# P11_Exp_Conn_uSD_and.net
KiCad netlist of a schematic drawn in Altium Designer
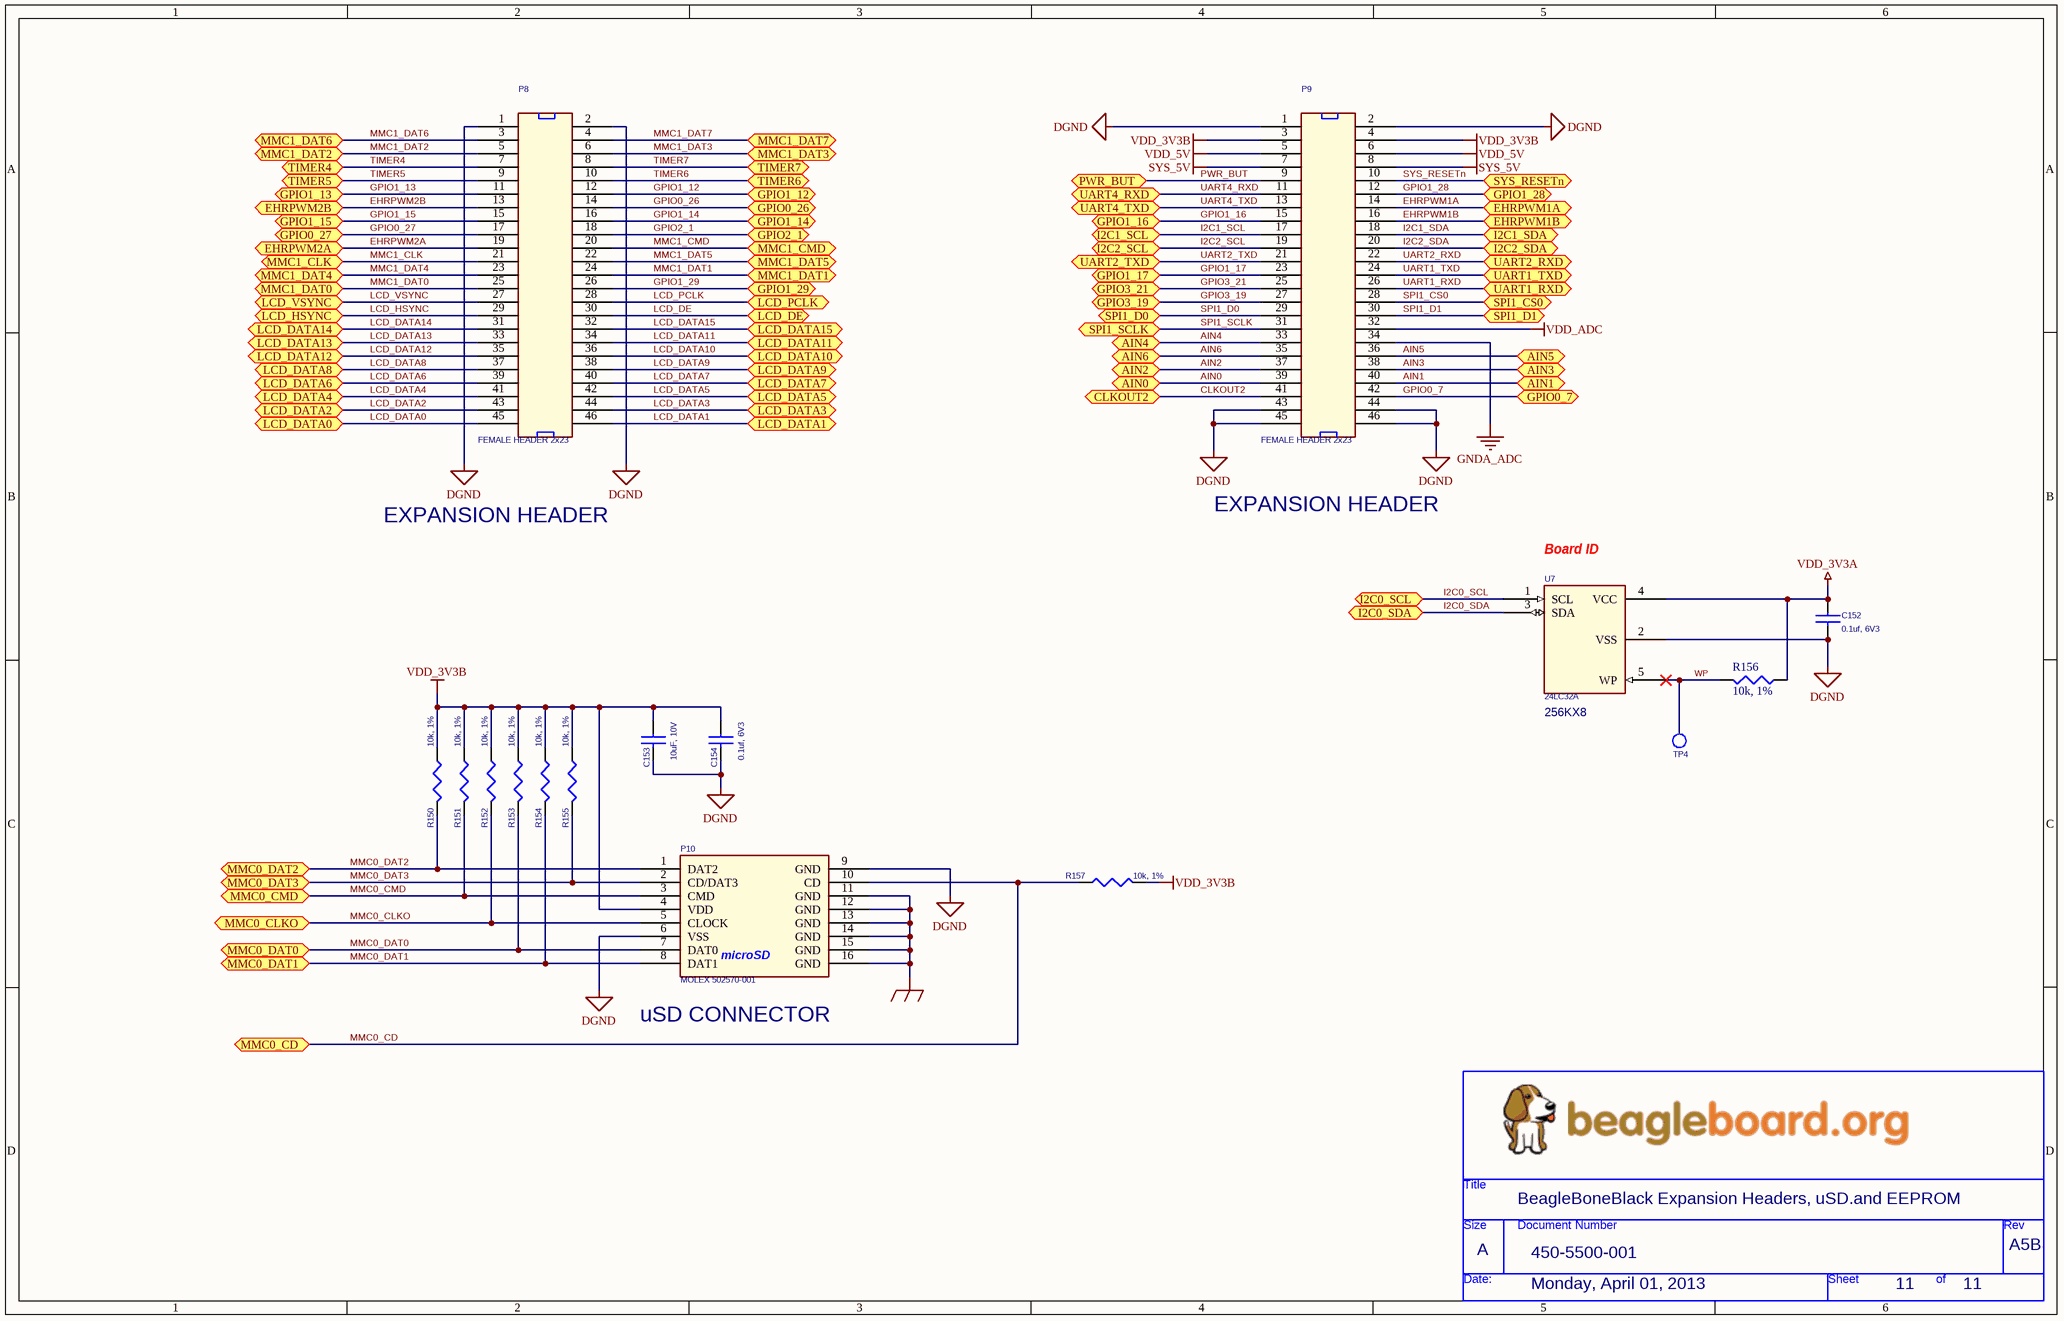
[diagram p0: P11_Exp Conn, uSD, and .SchDoc]

(export (version "E")
  (design (tool "Eeschema 10.0.6"))
  (components
    (comp (ref "C152")
      (value "0.1uf, 6V3")
      (footprint "402")
      (description "CAP CER 0.1UF 6.3V 10% X5R 0402")
      (fields
        (field (name "MANUFACTURER") "TDK Corporation")
        (field (name "MANUFACTURER PART NUMBER") "C1005X5R0J104K050BA")
      )
      (libsource (lib "BEAGLEBONEBLACK_REV A5B") (part "CAP_0.1uF_X7R_16V_10% 0402"))
    )
    (comp (ref "C153")
      (value "10uF, 10V")
      (description "CAP CER 10UF 10V Y5V 0805")
      (fields
        (field (name "MANUFACTURER") "TDK Corporation")
        (field (name "MANUFACTURER PART NUMBER") "C2012Y5V1A106Z")
      )
      (libsource (lib "BEAGLEBONEBLACK_REV A5B") (part "CAP_10uF_Y5V_10V_10%_0805"))
    )
    (comp (ref "C154")
      (value "0.1uf, 6V3")
      (footprint "402")
      (description "CAP CER 0.1UF 6.3V 10% X5R 0402")
      (fields
        (field (name "MANUFACTURER") "TDK Corporation")
        (field (name "MANUFACTURER PART NUMBER") "C1005X5R0J104K050BA")
      )
      (libsource (lib "BEAGLEBONEBLACK_REV A5B") (part "CAP_0.1uF_X7R_16V_10% 0402"))
    )
    (comp (ref "P8")
      (value "FEMALE HEADER 2x23")
      (description "CONN HEADER FMAL 46PS.1\" DL GOLD")
      (fields
        (field (name "MANUFACTURER") "Sullins Connector Solutions")
        (field (name "MANUFACTURER PART NUMBER") "PPPC232LFBN-RC")
      )
      (libsource (lib "BEAGLEBONEBLACK_REV A5B") (part "HDR_46_F_2_0.1_0.1"))
    )
    (comp (ref "P9")
      (value "FEMALE HEADER 2x23")
      (description "CONN HEADER FMAL 46PS.1\" DL GOLD")
      (fields
        (field (name "MANUFACTURER") "Sullins Connector Solutions")
        (field (name "MANUFACTURER PART NUMBER") "PPPC232LFBN-RC")
      )
      (libsource (lib "BEAGLEBONEBLACK_REV A5B") (part "HDR_46_F_2_0.1_0.1"))
    )
    (comp (ref "P10")
      (value "MOLEX 502570-001")
      (footprint "SD-MICRO-SCHA5B0300")
      (description "CONN MICRO SD R/A PUSH-PUSH SMD")
      (fields
        (field (name "MANUFACTURER") "Molex Inc")
        (field (name "MANUFACTURER PART NUMBER") "5025700893")
      )
      (libsource (lib "BEAGLEBONEBLACK_REV A5B") (part "microSD_CONN_2"))
    )
    (comp (ref "R150")
      (value "10k, 1%")
      (footprint "402")
      (description "RES 10K OHM 1/16W 5% 0402 SMD")
      (fields
        (field (name "MANUFACTURER") "Rohm Semiconductor")
        (field (name "MANUFACTURER PART NUMBER") "MCR01MZPJ103")
      )
      (libsource (lib "BEAGLEBONEBLACK_REV A5B") (part "RES_10K_1/16W_1%_0402"))
    )
    (comp (ref "R151")
      (value "10k, 1%")
      (footprint "402")
      (description "RES 10K OHM 1/16W 5% 0402 SMD")
      (fields
        (field (name "MANUFACTURER") "Rohm Semiconductor")
        (field (name "MANUFACTURER PART NUMBER") "MCR01MZPJ103")
      )
      (libsource (lib "BEAGLEBONEBLACK_REV A5B") (part "RES_10K_1/16W_1%_0402"))
    )
    (comp (ref "R152")
      (value "10k, 1%")
      (footprint "402")
      (description "RES 10K OHM 1/16W 5% 0402 SMD")
      (fields
        (field (name "MANUFACTURER") "Rohm Semiconductor")
        (field (name "MANUFACTURER PART NUMBER") "MCR01MZPJ103")
      )
      (libsource (lib "BEAGLEBONEBLACK_REV A5B") (part "RES_10K_1/16W_1%_0402"))
    )
    (comp (ref "R153")
      (value "10k, 1%")
      (footprint "402")
      (description "RES 10K OHM 1/16W 5% 0402 SMD")
      (fields
        (field (name "MANUFACTURER") "Rohm Semiconductor")
        (field (name "MANUFACTURER PART NUMBER") "MCR01MZPJ103")
      )
      (libsource (lib "BEAGLEBONEBLACK_REV A5B") (part "RES_10K_1/16W_1%_0402"))
    )
    (comp (ref "R154")
      (value "10k, 1%")
      (footprint "402")
      (description "RES 10K OHM 1/16W 5% 0402 SMD")
      (fields
        (field (name "MANUFACTURER") "Rohm Semiconductor")
        (field (name "MANUFACTURER PART NUMBER") "MCR01MZPJ103")
      )
      (libsource (lib "BEAGLEBONEBLACK_REV A5B") (part "RES_10K_1/16W_1%_0402"))
    )
    (comp (ref "R155")
      (value "10k, 1%")
      (footprint "402")
      (description "RES 10K OHM 1/16W 5% 0402 SMD")
      (fields
        (field (name "MANUFACTURER") "Rohm Semiconductor")
        (field (name "MANUFACTURER PART NUMBER") "MCR01MZPJ103")
      )
      (libsource (lib "BEAGLEBONEBLACK_REV A5B") (part "RES_10K_1/16W_1%_0402"))
    )
    (comp (ref "R156")
      (value "10k, 1%")
      (footprint "402")
      (description "RES 10K OHM 1/16W 5% 0402 SMD")
      (fields
        (field (name "MANUFACTURER") "Rohm Semiconductor")
        (field (name "MANUFACTURER PART NUMBER") "MCR01MZPJ103")
      )
      (libsource (lib "BEAGLEBONEBLACK_REV A5B") (part "RES_10K_1/16W_1%_0402"))
    )
    (comp (ref "R157")
      (value "10k, 1%")
      (footprint "402")
      (description "RES 10K OHM 1/16W 5% 0402 SMD")
      (fields
        (field (name "MANUFACTURER") "Rohm Semiconductor")
        (field (name "MANUFACTURER PART NUMBER") "MCR01MZPJ103")
      )
      (libsource (lib "BEAGLEBONEBLACK_REV A5B") (part "RES_10K_1/16W_1%_0402"))
    )
    (comp (ref "TP4")
      (value "TESTPT1")
      (footprint "tp1-8040")
      (libsource (lib "BEAGLEBONEBLACK_REV A5B") (part "TESTPT1"))
    )
    (comp (ref "U7")
      (value "24LC32A")
      (footprint "SOT23-5")
      (description "IC EEPROM 32KBIT 400KHZ SOT23-5")
      (fields
        (field (name "MANUFACTURER") "Microchip Technology")
        (field (name "MANUFACTURER PART NUMBER") "24LC32AT-I/OT")
      )
      (libsource (lib "BEAGLEBONEBLACK_REV A5B") (part "24LC32A"))
    )
  )
  (nets
    (net (code "1") (name "/AIN0") (class "Default")
      (node (ref "P9") (pin "39") (pinfunction "20_39") (pintype "passive"))
    )
    (net (code "2") (name "/AIN1") (class "Default")
      (node (ref "P9") (pin "40") (pinfunction "45_40") (pintype "passive"))
    )
    (net (code "3") (name "/AIN2") (class "Default")
      (node (ref "P9") (pin "37") (pinfunction "19_37") (pintype "passive"))
    )
    (net (code "4") (name "/AIN3") (class "Default")
      (node (ref "P9") (pin "38") (pinfunction "44_38") (pintype "passive"))
    )
    (net (code "5") (name "/AIN4") (class "Default")
      (node (ref "P9") (pin "33") (pinfunction "17_33") (pintype "passive"))
    )
    (net (code "6") (name "/AIN5") (class "Default")
      (node (ref "P9") (pin "36") (pinfunction "43_36") (pintype "passive"))
    )
    (net (code "7") (name "/AIN6") (class "Default")
      (node (ref "P9") (pin "35") (pinfunction "18_35") (pintype "passive"))
    )
    (net (code "8") (name "/CLKOUT2") (class "Default")
      (node (ref "P9") (pin "41") (pinfunction "21_41") (pintype "passive"))
    )
    (net (code "9") (name "/EHRPWM1A") (class "Default")
      (node (ref "P9") (pin "14") (pinfunction "32_14") (pintype "passive"))
    )
    (net (code "10") (name "/EHRPWM1B") (class "Default")
      (node (ref "P9") (pin "16") (pinfunction "33_16") (pintype "passive"))
    )
    (net (code "11") (name "/EHRPWM2A") (class "Default")
      (node (ref "P8") (pin "19") (pinfunction "10_19") (pintype "passive"))
    )
    (net (code "12") (name "/EHRPWM2B") (class "Default")
      (node (ref "P8") (pin "13") (pinfunction "7_13") (pintype "passive"))
    )
    (net (code "13") (name "/GPIO0_7") (class "Default")
      (node (ref "P9") (pin "42") (pinfunction "46_42") (pintype "passive"))
    )
    (net (code "14") (name "/GPIO0_26") (class "Default")
      (node (ref "P8") (pin "14") (pinfunction "32_14") (pintype "passive"))
    )
    (net (code "15") (name "/GPIO0_27") (class "Default")
      (node (ref "P8") (pin "17") (pinfunction "9_17") (pintype "passive"))
    )
    (net (code "16") (name "/GPIO1_12") (class "Default")
      (node (ref "P8") (pin "12") (pinfunction "31_12") (pintype "passive"))
    )
    (net (code "17") (name "/GPIO1_13") (class "Default")
      (node (ref "P8") (pin "11") (pinfunction "6_11") (pintype "passive"))
    )
    (net (code "18") (name "/GPIO1_14") (class "Default")
      (node (ref "P8") (pin "16") (pinfunction "33_16") (pintype "passive"))
    )
    (net (code "19") (name "/GPIO1_15") (class "Default")
      (node (ref "P8") (pin "15") (pinfunction "8_15") (pintype "passive"))
    )
    (net (code "20") (name "/GPIO1_16") (class "Default")
      (node (ref "P9") (pin "15") (pinfunction "8_15") (pintype "passive"))
    )
    (net (code "21") (name "/GPIO1_17") (class "Default")
      (node (ref "P9") (pin "23") (pinfunction "12_23") (pintype "passive"))
    )
    (net (code "22") (name "/GPIO1_28") (class "Default")
      (node (ref "P9") (pin "12") (pinfunction "31_12") (pintype "passive"))
    )
    (net (code "23") (name "/GPIO1_29") (class "Default")
      (node (ref "P8") (pin "26") (pinfunction "38_26") (pintype "passive"))
    )
    (net (code "24") (name "/GPIO2_1") (class "Default")
      (node (ref "P8") (pin "18") (pinfunction "34_18") (pintype "passive"))
    )
    (net (code "25") (name "/GPIO3_19") (class "Default")
      (node (ref "P9") (pin "27") (pinfunction "14_27") (pintype "passive"))
    )
    (net (code "26") (name "/GPIO3_21") (class "Default")
      (node (ref "P9") (pin "25") (pinfunction "13_25") (pintype "passive"))
    )
    (net (code "27") (name "/I2C0_SCL") (class "Default")
      (node (ref "U7") (pin "1") (pinfunction "SCL_1") (pintype "input"))
    )
    (net (code "28") (name "/I2C0_SDA") (class "Default")
      (node (ref "U7") (pin "3") (pinfunction "SDA_3") (pintype "bidirectional"))
    )
    (net (code "29") (name "/I2C1_SCL") (class "Default")
      (node (ref "P9") (pin "17") (pinfunction "9_17") (pintype "passive"))
    )
    (net (code "30") (name "/I2C1_SDA") (class "Default")
      (node (ref "P9") (pin "18") (pinfunction "34_18") (pintype "passive"))
    )
    (net (code "31") (name "/I2C2_SCL") (class "Default")
      (node (ref "P9") (pin "19") (pinfunction "10_19") (pintype "passive"))
    )
    (net (code "32") (name "/I2C2_SDA") (class "Default")
      (node (ref "P9") (pin "20") (pinfunction "35_20") (pintype "passive"))
    )
    (net (code "33") (name "/LCD_DATA0") (class "Default")
      (node (ref "P8") (pin "45") (pinfunction "23_45") (pintype "passive"))
    )
    (net (code "34") (name "/LCD_DATA1") (class "Default")
      (node (ref "P8") (pin "46") (pinfunction "48_46") (pintype "passive"))
    )
    (net (code "35") (name "/LCD_DATA2") (class "Default")
      (node (ref "P8") (pin "43") (pinfunction "22_43") (pintype "passive"))
    )
    (net (code "36") (name "/LCD_DATA3") (class "Default")
      (node (ref "P8") (pin "44") (pinfunction "47_44") (pintype "passive"))
    )
    (net (code "37") (name "/LCD_DATA4") (class "Default")
      (node (ref "P8") (pin "41") (pinfunction "21_41") (pintype "passive"))
    )
    (net (code "38") (name "/LCD_DATA5") (class "Default")
      (node (ref "P8") (pin "42") (pinfunction "46_42") (pintype "passive"))
    )
    (net (code "39") (name "/LCD_DATA6") (class "Default")
      (node (ref "P8") (pin "39") (pinfunction "20_39") (pintype "passive"))
    )
    (net (code "40") (name "/LCD_DATA7") (class "Default")
      (node (ref "P8") (pin "40") (pinfunction "45_40") (pintype "passive"))
    )
    (net (code "41") (name "/LCD_DATA8") (class "Default")
      (node (ref "P8") (pin "37") (pinfunction "19_37") (pintype "passive"))
    )
    (net (code "42") (name "/LCD_DATA9") (class "Default")
      (node (ref "P8") (pin "38") (pinfunction "44_38") (pintype "passive"))
    )
    (net (code "43") (name "/LCD_DATA10") (class "Default")
      (node (ref "P8") (pin "36") (pinfunction "43_36") (pintype "passive"))
    )
    (net (code "44") (name "/LCD_DATA11") (class "Default")
      (node (ref "P8") (pin "34") (pinfunction "42_34") (pintype "passive"))
    )
    (net (code "45") (name "/LCD_DATA12") (class "Default")
      (node (ref "P8") (pin "35") (pinfunction "18_35") (pintype "passive"))
    )
    (net (code "46") (name "/LCD_DATA13") (class "Default")
      (node (ref "P8") (pin "33") (pinfunction "17_33") (pintype "passive"))
    )
    (net (code "47") (name "/LCD_DATA14") (class "Default")
      (node (ref "P8") (pin "31") (pinfunction "16_31") (pintype "passive"))
    )
    (net (code "48") (name "/LCD_DATA15") (class "Default")
      (node (ref "P8") (pin "32") (pinfunction "41_32") (pintype "passive"))
    )
    (net (code "49") (name "/LCD_DE") (class "Default")
      (node (ref "P8") (pin "30") (pinfunction "40_30") (pintype "passive"))
    )
    (net (code "50") (name "/LCD_HSYNC") (class "Default")
      (node (ref "P8") (pin "29") (pinfunction "15_29") (pintype "passive"))
    )
    (net (code "51") (name "/LCD_PCLK") (class "Default")
      (node (ref "P8") (pin "28") (pinfunction "39_28") (pintype "passive"))
    )
    (net (code "52") (name "/LCD_VSYNC") (class "Default")
      (node (ref "P8") (pin "27") (pinfunction "14_27") (pintype "passive"))
    )
    (net (code "53") (name "/MMC0_CD") (class "Default")
      (node (ref "P10") (pin "10") (pinfunction "CD_10") (pintype "passive"))
      (node (ref "R157") (pin "1") (pinfunction "1_1") (pintype "passive"))
    )
    (net (code "54") (name "/MMC0_CLKO") (class "Default")
      (node (ref "P10") (pin "5") (pinfunction "CLOCK_5") (pintype "passive"))
      (node (ref "R152") (pin "2") (pinfunction "2_2") (pintype "passive"))
    )
    (net (code "55") (name "/MMC0_CMD") (class "Default")
      (node (ref "P10") (pin "3") (pinfunction "CMD_3") (pintype "passive"))
      (node (ref "R151") (pin "2") (pinfunction "2_2") (pintype "passive"))
    )
    (net (code "56") (name "/MMC0_DAT0") (class "Default")
      (node (ref "P10") (pin "7") (pinfunction "DAT0_7") (pintype "passive"))
      (node (ref "R153") (pin "2") (pinfunction "2_2") (pintype "passive"))
    )
    (net (code "57") (name "/MMC0_DAT1") (class "Default")
      (node (ref "P10") (pin "8") (pinfunction "DAT1_8") (pintype "passive"))
      (node (ref "R154") (pin "2") (pinfunction "2_2") (pintype "passive"))
    )
    (net (code "58") (name "/MMC0_DAT2") (class "Default")
      (node (ref "P10") (pin "1") (pinfunction "DAT2_1") (pintype "passive"))
      (node (ref "R150") (pin "2") (pinfunction "2_2") (pintype "passive"))
    )
    (net (code "59") (name "/MMC0_DAT3") (class "Default")
      (node (ref "P10") (pin "2") (pinfunction "CD/DAT3_2") (pintype "passive"))
      (node (ref "R155") (pin "2") (pinfunction "2_2") (pintype "passive"))
    )
    (net (code "60") (name "/MMC1_CLK") (class "Default")
      (node (ref "P8") (pin "21") (pinfunction "11_21") (pintype "passive"))
    )
    (net (code "61") (name "/MMC1_CMD") (class "Default")
      (node (ref "P8") (pin "20") (pinfunction "35_20") (pintype "passive"))
    )
    (net (code "62") (name "/MMC1_DAT0") (class "Default")
      (node (ref "P8") (pin "25") (pinfunction "13_25") (pintype "passive"))
    )
    (net (code "63") (name "/MMC1_DAT1") (class "Default")
      (node (ref "P8") (pin "24") (pinfunction "37_24") (pintype "passive"))
    )
    (net (code "64") (name "/MMC1_DAT2") (class "Default")
      (node (ref "P8") (pin "5") (pinfunction "3_5") (pintype "passive"))
    )
    (net (code "65") (name "/MMC1_DAT3") (class "Default")
      (node (ref "P8") (pin "6") (pinfunction "28_6") (pintype "passive"))
    )
    (net (code "66") (name "/MMC1_DAT4") (class "Default")
      (node (ref "P8") (pin "23") (pinfunction "12_23") (pintype "passive"))
    )
    (net (code "67") (name "/MMC1_DAT5") (class "Default")
      (node (ref "P8") (pin "22") (pinfunction "36_22") (pintype "passive"))
    )
    (net (code "68") (name "/MMC1_DAT6") (class "Default")
      (node (ref "P8") (pin "3") (pinfunction "2_3") (pintype "passive"))
    )
    (net (code "69") (name "/MMC1_DAT7") (class "Default")
      (node (ref "P8") (pin "4") (pinfunction "27_4") (pintype "passive"))
    )
    (net (code "70") (name "/PWR_BUT") (class "Default")
      (node (ref "P9") (pin "9") (pinfunction "5_9") (pintype "passive"))
    )
    (net (code "71") (name "/SPI1_CS0") (class "Default")
      (node (ref "P9") (pin "28") (pinfunction "39_28") (pintype "passive"))
    )
    (net (code "72") (name "/SPI1_D0") (class "Default")
      (node (ref "P9") (pin "29") (pinfunction "15_29") (pintype "passive"))
    )
    (net (code "73") (name "/SPI1_D1") (class "Default")
      (node (ref "P9") (pin "30") (pinfunction "40_30") (pintype "passive"))
    )
    (net (code "74") (name "/SPI1_SCLK") (class "Default")
      (node (ref "P9") (pin "31") (pinfunction "16_31") (pintype "passive"))
    )
    (net (code "75") (name "/SYS_RESETn") (class "Default")
      (node (ref "P9") (pin "10") (pinfunction "30_10") (pintype "passive"))
    )
    (net (code "76") (name "/TIMER4") (class "Default")
      (node (ref "P8") (pin "7") (pinfunction "4_7") (pintype "passive"))
    )
    (net (code "77") (name "/TIMER5") (class "Default")
      (node (ref "P8") (pin "9") (pinfunction "5_9") (pintype "passive"))
    )
    (net (code "78") (name "/TIMER6") (class "Default")
      (node (ref "P8") (pin "10") (pinfunction "30_10") (pintype "passive"))
    )
    (net (code "79") (name "/TIMER7") (class "Default")
      (node (ref "P8") (pin "8") (pinfunction "29_8") (pintype "passive"))
    )
    (net (code "80") (name "/UART1_RXD") (class "Default")
      (node (ref "P9") (pin "26") (pinfunction "38_26") (pintype "passive"))
    )
    (net (code "81") (name "/UART1_TXD") (class "Default")
      (node (ref "P9") (pin "24") (pinfunction "37_24") (pintype "passive"))
    )
    (net (code "82") (name "/UART2_RXD") (class "Default")
      (node (ref "P9") (pin "22") (pinfunction "36_22") (pintype "passive"))
    )
    (net (code "83") (name "/UART2_TXD") (class "Default")
      (node (ref "P9") (pin "21") (pinfunction "11_21") (pintype "passive"))
    )
    (net (code "84") (name "/UART4_RXD") (class "Default")
      (node (ref "P9") (pin "11") (pinfunction "6_11") (pintype "passive"))
    )
    (net (code "85") (name "/UART4_TXD") (class "Default")
      (node (ref "P9") (pin "13") (pinfunction "7_13") (pintype "passive"))
    )
    (net (code "86") (name "/WP") (class "Default")
      (node (ref "R156") (pin "2") (pinfunction "2_2") (pintype "passive"))
      (node (ref "TP4") (pin "1") (pinfunction "TP_1") (pintype "passive"))
      (node (ref "U7") (pin "5") (pinfunction "WP_5") (pintype "input"))
    )
    (net (code "87") (name "DGND") (class "Default")
      (node (ref "C152") (pin "2") (pinfunction "2_2") (pintype "passive"))
      (node (ref "C153") (pin "2") (pinfunction "2_2") (pintype "passive"))
      (node (ref "C154") (pin "2") (pinfunction "2_2") (pintype "passive"))
      (node (ref "P10") (pin "6") (pinfunction "VSS_6") (pintype "power_in"))
      (node (ref "P10") (pin "9") (pinfunction "GND_9") (pintype "power_in"))
      (node (ref "P8") (pin "1") (pinfunction "1_1") (pintype "passive"))
      (node (ref "P8") (pin "2") (pinfunction "26_2") (pintype "passive"))
      (node (ref "P9") (pin "1") (pinfunction "1_1") (pintype "passive"))
      (node (ref "P9") (pin "2") (pinfunction "26_2") (pintype "passive"))
      (node (ref "P9") (pin "43") (pinfunction "22_43") (pintype "passive"))
      (node (ref "P9") (pin "44") (pinfunction "47_44") (pintype "passive"))
      (node (ref "P9") (pin "45") (pinfunction "23_45") (pintype "passive"))
      (node (ref "P9") (pin "46") (pinfunction "48_46") (pintype "passive"))
      (node (ref "U7") (pin "2") (pinfunction "VSS_2") (pintype "power_in"))
    )
    (net (code "88") (name "GNDA_ADC") (class "Default")
      (node (ref "P9") (pin "34") (pinfunction "42_34") (pintype "passive"))
    )
    (net (code "89") (name "GND_EARTH") (class "Default")
      (node (ref "P10") (pin "11") (pinfunction "GND_11") (pintype "power_in"))
      (node (ref "P10") (pin "12") (pinfunction "GND_12") (pintype "power_in"))
      (node (ref "P10") (pin "13") (pinfunction "GND_13") (pintype "passive"))
      (node (ref "P10") (pin "14") (pinfunction "GND_14") (pintype "passive"))
      (node (ref "P10") (pin "15") (pinfunction "GND_15") (pintype "passive"))
      (node (ref "P10") (pin "16") (pinfunction "GND_16") (pintype "passive"))
    )
    (net (code "90") (name "SYS_5V") (class "Default")
      (node (ref "P9") (pin "7") (pinfunction "4_7") (pintype "passive"))
      (node (ref "P9") (pin "8") (pinfunction "29_8") (pintype "passive"))
    )
    (net (code "91") (name "VDD_3V3A") (class "Default")
      (node (ref "C152") (pin "1") (pinfunction "1_1") (pintype "passive"))
      (node (ref "R156") (pin "1") (pinfunction "1_1") (pintype "passive"))
      (node (ref "U7") (pin "4") (pinfunction "VCC_4") (pintype "power_in"))
    )
    (net (code "92") (name "VDD_3V3B") (class "Default")
      (node (ref "C153") (pin "1") (pinfunction "1_1") (pintype "passive"))
      (node (ref "C154") (pin "1") (pinfunction "1_1") (pintype "passive"))
      (node (ref "P10") (pin "4") (pinfunction "VDD_4") (pintype "power_in"))
      (node (ref "P9") (pin "3") (pinfunction "2_3") (pintype "passive"))
      (node (ref "P9") (pin "4") (pinfunction "27_4") (pintype "passive"))
      (node (ref "R150") (pin "1") (pinfunction "1_1") (pintype "passive"))
      (node (ref "R151") (pin "1") (pinfunction "1_1") (pintype "passive"))
      (node (ref "R152") (pin "1") (pinfunction "1_1") (pintype "passive"))
      (node (ref "R153") (pin "1") (pinfunction "1_1") (pintype "passive"))
      (node (ref "R154") (pin "1") (pinfunction "1_1") (pintype "passive"))
      (node (ref "R155") (pin "1") (pinfunction "1_1") (pintype "passive"))
      (node (ref "R157") (pin "2") (pinfunction "2_2") (pintype "passive"))
    )
    (net (code "93") (name "VDD_5V") (class "Default")
      (node (ref "P9") (pin "5") (pinfunction "3_5") (pintype "passive"))
      (node (ref "P9") (pin "6") (pinfunction "28_6") (pintype "passive"))
    )
    (net (code "94") (name "VDD_ADC") (class "Default")
      (node (ref "P9") (pin "32") (pinfunction "41_32") (pintype "passive"))
    )
  )
)
